# User_buttom.net
KiCad netlist of a schematic drawn in Altium Designer
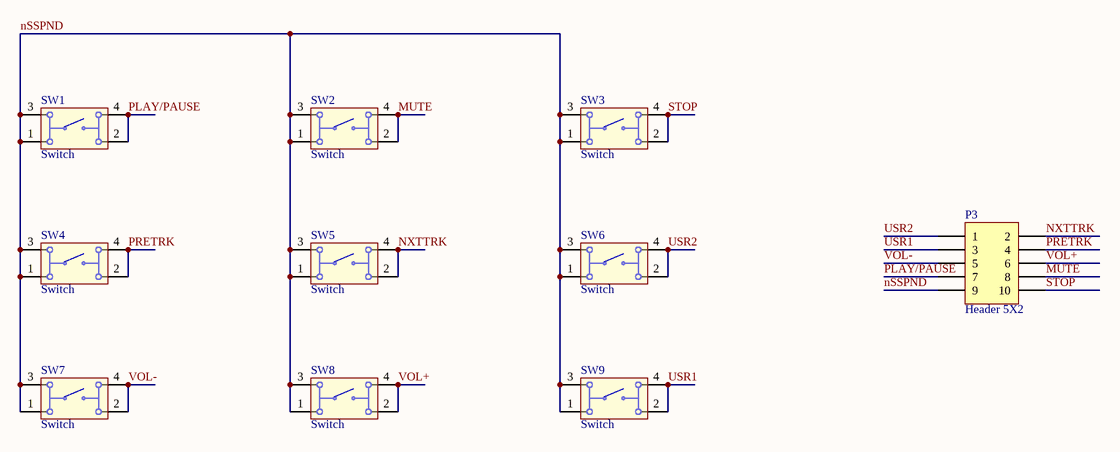
[diagram p0: User_buttom.SchDoc]

(export (version "E")
  (design (tool "Eeschema 10.0.6"))
  (components
    (comp (ref "P3")
      (value "Header 5X2")
      (footprint "HDR2X5")
      (description "Header, 5-Pin, Dual row")
      (fields (field (name "PUBLISHER") "Altium Limited"))
      (libsource (lib "Miscellaneous Connectors") (part "Header 5X2"))
    )
    (comp (ref "SW1")
      (value "Switch")
      (footprint "430156050726")
      (description "WS-TATV THT Tact Switch 6X6 mm")
      (fields (field (name "PARTNUMBER") "430156050726"))
      (libsource (lib "WS-TATV THT Tact Switch 6X6 mm") (part "430156050726"))
    )
    (comp (ref "SW2")
      (value "Switch")
      (footprint "430156050726")
      (description "WS-TATV THT Tact Switch 6X6 mm")
      (fields (field (name "PARTNUMBER") "430156050726"))
      (libsource (lib "WS-TATV THT Tact Switch 6X6 mm") (part "430156050726"))
    )
    (comp (ref "SW3")
      (value "Switch")
      (footprint "430156050726")
      (description "WS-TATV THT Tact Switch 6X6 mm")
      (fields (field (name "PARTNUMBER") "430156050726"))
      (libsource (lib "WS-TATV THT Tact Switch 6X6 mm") (part "430156050726"))
    )
    (comp (ref "SW4")
      (value "Switch")
      (footprint "430156050726")
      (description "WS-TATV THT Tact Switch 6X6 mm")
      (fields (field (name "PARTNUMBER") "430156050726"))
      (libsource (lib "WS-TATV THT Tact Switch 6X6 mm") (part "430156050726"))
    )
    (comp (ref "SW5")
      (value "Switch")
      (footprint "430156050726")
      (description "WS-TATV THT Tact Switch 6X6 mm")
      (fields (field (name "PARTNUMBER") "430156050726"))
      (libsource (lib "WS-TATV THT Tact Switch 6X6 mm") (part "430156050726"))
    )
    (comp (ref "SW6")
      (value "Switch")
      (footprint "430156050726")
      (description "WS-TATV THT Tact Switch 6X6 mm")
      (fields (field (name "PARTNUMBER") "430156050726"))
      (libsource (lib "WS-TATV THT Tact Switch 6X6 mm") (part "430156050726"))
    )
    (comp (ref "SW7")
      (value "Switch")
      (footprint "430156050726")
      (description "WS-TATV THT Tact Switch 6X6 mm")
      (fields (field (name "PARTNUMBER") "430156050726"))
      (libsource (lib "WS-TATV THT Tact Switch 6X6 mm") (part "430156050726"))
    )
    (comp (ref "SW8")
      (value "Switch")
      (footprint "430156050726")
      (description "WS-TATV THT Tact Switch 6X6 mm")
      (fields (field (name "PARTNUMBER") "430156050726"))
      (libsource (lib "WS-TATV THT Tact Switch 6X6 mm") (part "430156050726"))
    )
    (comp (ref "SW9")
      (value "Switch")
      (footprint "430156050726")
      (description "WS-TATV THT Tact Switch 6X6 mm")
      (fields (field (name "PARTNUMBER") "430156050726"))
      (libsource (lib "WS-TATV THT Tact Switch 6X6 mm") (part "430156050726"))
    )
  )
  (nets
    (net (code "1") (name "/MUTE") (class "Default")
      (node (ref "P3") (pin "8") (pinfunction "8_8") (pintype "passive"))
      (node (ref "SW2") (pin "2") (pinfunction "2_2") (pintype "passive"))
      (node (ref "SW2") (pin "4") (pinfunction "4_4") (pintype "passive"))
    )
    (net (code "2") (name "/NXTTRK") (class "Default")
      (node (ref "P3") (pin "2") (pinfunction "2_2") (pintype "passive"))
      (node (ref "SW5") (pin "2") (pinfunction "2_2") (pintype "passive"))
      (node (ref "SW5") (pin "4") (pinfunction "4_4") (pintype "passive"))
    )
    (net (code "3") (name "/PLAY{slash}PAUSE") (class "Default")
      (node (ref "P3") (pin "7") (pinfunction "7_7") (pintype "passive"))
      (node (ref "SW1") (pin "2") (pinfunction "2_2") (pintype "passive"))
      (node (ref "SW1") (pin "4") (pinfunction "4_4") (pintype "passive"))
    )
    (net (code "4") (name "/PRETRK") (class "Default")
      (node (ref "P3") (pin "4") (pinfunction "4_4") (pintype "passive"))
      (node (ref "SW4") (pin "2") (pinfunction "2_2") (pintype "passive"))
      (node (ref "SW4") (pin "4") (pinfunction "4_4") (pintype "passive"))
    )
    (net (code "5") (name "/STOP") (class "Default")
      (node (ref "P3") (pin "10") (pinfunction "10_10") (pintype "passive"))
      (node (ref "SW3") (pin "2") (pinfunction "2_2") (pintype "passive"))
      (node (ref "SW3") (pin "4") (pinfunction "4_4") (pintype "passive"))
    )
    (net (code "6") (name "/USR1") (class "Default")
      (node (ref "P3") (pin "3") (pinfunction "3_3") (pintype "passive"))
      (node (ref "SW9") (pin "2") (pinfunction "2_2") (pintype "passive"))
      (node (ref "SW9") (pin "4") (pinfunction "4_4") (pintype "passive"))
    )
    (net (code "7") (name "/USR2") (class "Default")
      (node (ref "P3") (pin "1") (pinfunction "1_1") (pintype "passive"))
      (node (ref "SW6") (pin "2") (pinfunction "2_2") (pintype "passive"))
      (node (ref "SW6") (pin "4") (pinfunction "4_4") (pintype "passive"))
    )
    (net (code "8") (name "/VOL+") (class "Default")
      (node (ref "P3") (pin "6") (pinfunction "6_6") (pintype "passive"))
      (node (ref "SW8") (pin "2") (pinfunction "2_2") (pintype "passive"))
      (node (ref "SW8") (pin "4") (pinfunction "4_4") (pintype "passive"))
    )
    (net (code "9") (name "/VOL-") (class "Default")
      (node (ref "P3") (pin "5") (pinfunction "5_5") (pintype "passive"))
      (node (ref "SW7") (pin "2") (pinfunction "2_2") (pintype "passive"))
      (node (ref "SW7") (pin "4") (pinfunction "4_4") (pintype "passive"))
    )
    (net (code "10") (name "/nSSPND") (class "Default")
      (node (ref "P3") (pin "9") (pinfunction "9_9") (pintype "passive"))
      (node (ref "SW1") (pin "1") (pinfunction "1_1") (pintype "passive"))
      (node (ref "SW1") (pin "3") (pinfunction "3_3") (pintype "passive"))
      (node (ref "SW2") (pin "1") (pinfunction "1_1") (pintype "passive"))
      (node (ref "SW2") (pin "3") (pinfunction "3_3") (pintype "passive"))
      (node (ref "SW3") (pin "1") (pinfunction "1_1") (pintype "passive"))
      (node (ref "SW3") (pin "3") (pinfunction "3_3") (pintype "passive"))
      (node (ref "SW4") (pin "1") (pinfunction "1_1") (pintype "passive"))
      (node (ref "SW4") (pin "3") (pinfunction "3_3") (pintype "passive"))
      (node (ref "SW5") (pin "1") (pinfunction "1_1") (pintype "passive"))
      (node (ref "SW5") (pin "3") (pinfunction "3_3") (pintype "passive"))
      (node (ref "SW6") (pin "1") (pinfunction "1_1") (pintype "passive"))
      (node (ref "SW6") (pin "3") (pinfunction "3_3") (pintype "passive"))
      (node (ref "SW7") (pin "1") (pinfunction "1_1") (pintype "passive"))
      (node (ref "SW7") (pin "3") (pinfunction "3_3") (pintype "passive"))
      (node (ref "SW8") (pin "1") (pinfunction "1_1") (pintype "passive"))
      (node (ref "SW8") (pin "3") (pinfunction "3_3") (pintype "passive"))
      (node (ref "SW9") (pin "1") (pinfunction "1_1") (pintype "passive"))
      (node (ref "SW9") (pin "3") (pinfunction "3_3") (pintype "passive"))
    )
  )
)
